# Power_Input.net
KiCad netlist of a schematic drawn in Altium Designer
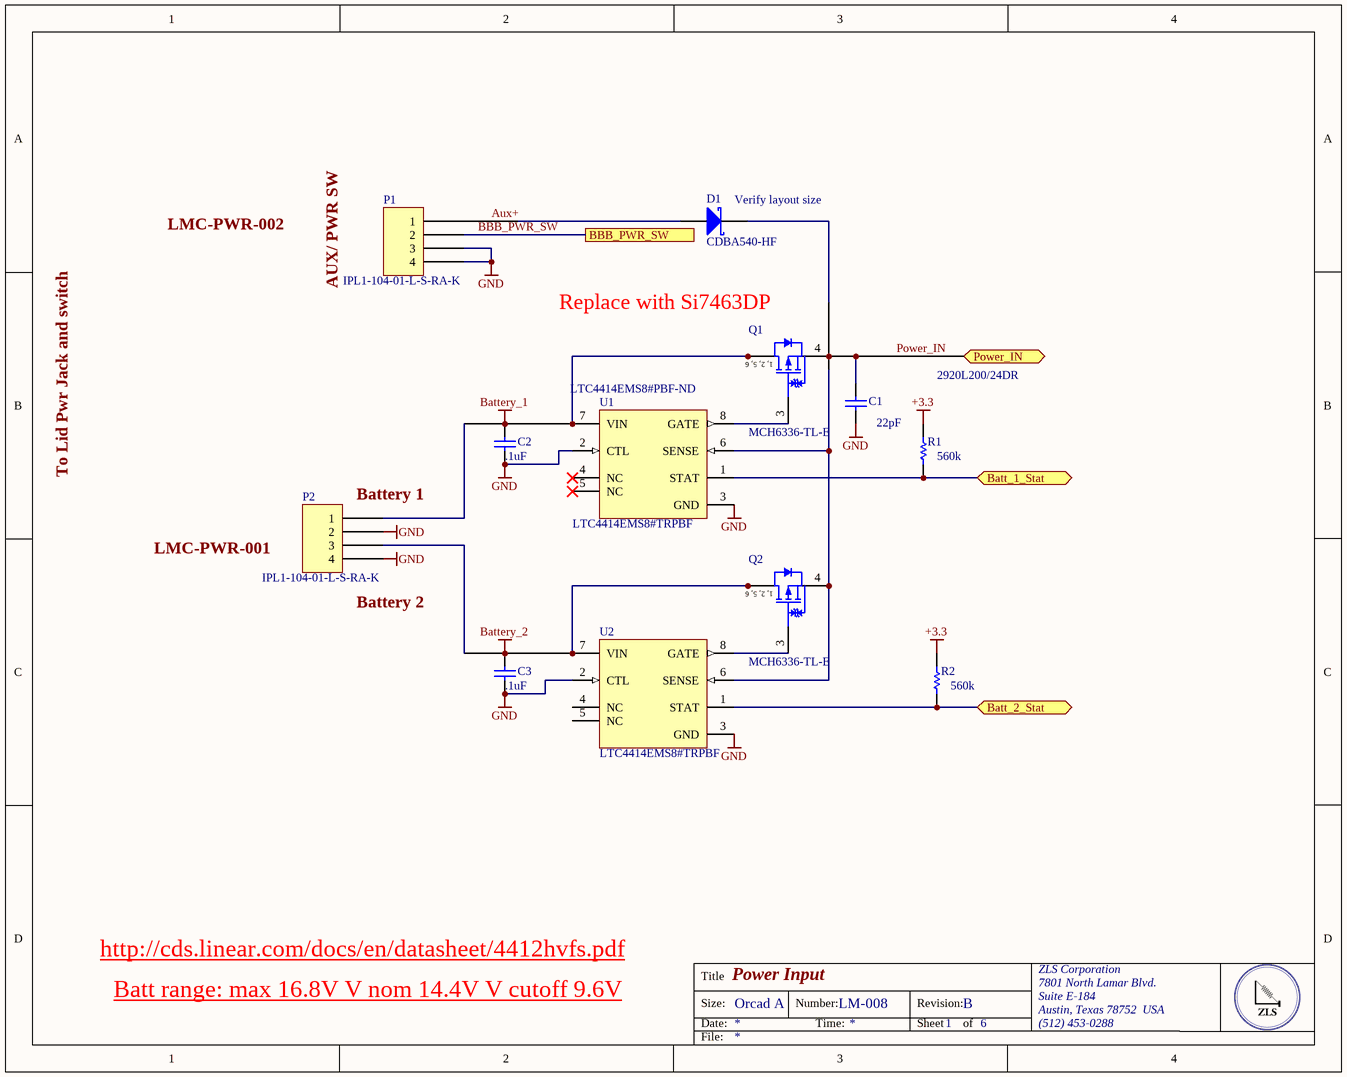
[diagram p0: Power_Input.SchDoc]

(export (version "E")
  (design (tool "Eeschema 10.0.6"))
  (components
    (comp (ref "C1")
      (value "CAP CER 10UF 6.3V X5R 1206")
      (footprint "CAPC1206(3216)130_N")
      (fields
        (field (name "MANUFACTURER") "Taiyo Yuden")
        (field (name "MANUFACTURER PART NUMBER") "JMK316BJ106ML-T")
        (field (name "TOLERANCE") "±20%")
        (field (name "CAPACITANCE") "22pF")
      )
      (libsource (lib "Altium Content Vault") (part "CMP-1037-04913-1"))
    )
    (comp (ref "C2")
      (value "CAP CER 10UF 6.3V X5R 1206")
      (footprint "CAPC1206(3216)130_N")
      (fields
        (field (name "MANUFACTURER") "Taiyo Yuden")
        (field (name "MANUFACTURER PART NUMBER") "JMK316BJ106ML-T")
        (field (name "TOLERANCE") "±20%")
        (field (name "CAPACITANCE") ".1uF")
      )
      (libsource (lib "Altium Content Vault") (part "CMP-1037-04913-1"))
    )
    (comp (ref "C3")
      (value "CAP CER 10UF 6.3V X5R 1206")
      (footprint "CAPC1206(3216)130_N")
      (fields
        (field (name "MANUFACTURER") "Taiyo Yuden")
        (field (name "MANUFACTURER PART NUMBER") "JMK316BJ106ML-T")
        (field (name "TOLERANCE") "±20%")
        (field (name "CAPACITANCE") ".1uF")
      )
      (libsource (lib "Altium Content Vault") (part "CMP-1037-04913-1"))
    )
    (comp (ref "D1")
      (value "CDBA540-HF")
      (footprint "VISH-DO-214AC-2_M")
      (description "DIODE SCHOTTKY 40V 5A DO214AB")
      (fields (field (name "MANUFACTURER") "Comchip Technology"))
      (libsource (lib "Miscellaneous Devices") (part "D Schottky"))
    )
    (comp (ref "P1")
      (value "IPL1-104-01-L-S-RA-K")
      (footprint "IPL1-104-01-L-S-RA-K")
      (fields
        (field (name "MANUFACTURER") "Samtec Inc.")
        (field (name "MANUFACTURER PART NUMBER") "IPL1-104-01-L-S-RA-K")
      )
      (libsource (lib "ZLS_Schematic_lib") (part "IPL1-104-01-L-S-RA-K"))
    )
    (comp (ref "P2")
      (value "IPL1-104-01-L-S-RA-K")
      (footprint "IPL1-104-01-L-S-RA-K")
      (fields
        (field (name "MANUFACTURER") "Samtec Inc.")
        (field (name "MANUFACTURER PART NUMBER") "IPL1-104-01-L-S-RA-K")
      )
      (libsource (lib "ZLS_Schematic_lib") (part "IPL1-104-01-L-S-RA-K"))
    )
    (comp (ref "Q1")
      (value "MCH6336-TL-E")
      (footprint "ONSC-MCPH-6_V")
      (description "P-Channel Power MOSFET, -12 V, -5 A, 43 mOhm, Single, 6-Pin MCPH, Pb-Free, Tape and Reel")
      (fields (field (name "MANUFACTURER") "ON Semiconductor"))
      (libsource (lib "Altium Content Vault") (part "CMP-1058-00598-1"))
    )
    (comp (ref "Q2")
      (value "MCH6336-TL-E")
      (footprint "ONSC-MCPH-6_V")
      (description "P-Channel Power MOSFET, -12 V, -5 A, 43 mOhm, Single, 6-Pin MCPH, Pb-Free, Tape and Reel")
      (fields (field (name "MANUFACTURER") "ON Semiconductor"))
      (libsource (lib "Altium Content Vault") (part "CMP-1058-00598-1"))
    )
    (comp (ref "R1")
      (value "560k")
      (footprint "RESC0402(1005)_L")
      (description "RES SMD 560K OHM 1% 1/10W 0402")
      (fields
        (field (name "MANUFACTURER") "Panasonic Electronic Components")
        (field (name "MANUFACTURER PART NUMBER") "ERJ-2RKF5603X")
      )
      (libsource (lib "Altium Content Vault") (part "CMP-1011-00927-1"))
    )
    (comp (ref "R2")
      (value "560k")
      (footprint "RESC0402(1005)_L")
      (description "RES SMD 560K OHM 1% 1/10W 0402")
      (fields
        (field (name "MANUFACTURER") "Panasonic Electronic Components")
        (field (name "MANUFACTURER PART NUMBER") "ERJ-2RKF5603X")
      )
      (libsource (lib "Altium Content Vault") (part "CMP-1011-00927-1"))
    )
    (comp (ref "U1")
      (value "LTC4414EMS8#TRPBF")
      (footprint "LT-MS8-8_L")
      (fields
        (field (name "SUPPLIER PART NUMBER 1") "LTC4414EMS8#PBF-ND")
        (field (name "MANUFACTURER") "Linear Technology/Analog Devices")
        (field (name "MANUFACTURER PART NUMBER") "LTC4414EMS8#PBF")
        (field (name "BASE PART NUMBER") "LTC4414")
      )
      (libsource (lib "Altium Content Vault") (part "CMP-0479-00214-1"))
    )
    (comp (ref "U2")
      (value "LTC4414EMS8#TRPBF")
      (footprint "LT-MS8-8_L")
      (fields
        (field (name "MANUFACTURER") "Linear Technology/Analog Devices")
        (field (name "MANUFACTURER PART NUMBER") "LTC4414EMS8#PBF")
        (field (name "BASE PART NUMBER") "LTC4414")
      )
      (libsource (lib "Altium Content Vault") (part "CMP-0479-00214-1"))
    )
  )
  (nets
    (net (code "1") (name "+3.3") (class "Default")
      (node (ref "R1") (pin "2") (pinfunction "2_2") (pintype "passive"))
      (node (ref "R2") (pin "2") (pinfunction "2_2") (pintype "passive"))
    )
    (net (code "2") (name "/Aux+") (class "Default")
      (node (ref "D1") (pin "1") (pinfunction "A_1") (pintype "passive"))
      (node (ref "P1") (pin "1") (pinfunction "1_1") (pintype "passive"))
    )
    (net (code "3") (name "/BBB_PWR_SW") (class "Default")
      (node (ref "P1") (pin "2") (pinfunction "2_2") (pintype "passive"))
    )
    (net (code "4") (name "/Batt_1_Stat") (class "Default")
      (node (ref "R1") (pin "1") (pinfunction "1_1") (pintype "passive"))
      (node (ref "U1") (pin "1") (pinfunction "STAT_1") (pintype "open_collector"))
    )
    (net (code "5") (name "/Batt_2_Stat") (class "Default")
      (node (ref "R2") (pin "1") (pinfunction "1_1") (pintype "passive"))
      (node (ref "U2") (pin "1") (pinfunction "STAT_1") (pintype "open_collector"))
    )
    (net (code "6") (name "/Power_IN") (class "Default")
      (node (ref "C1") (pin "2") (pinfunction "2_2") (pintype "passive"))
      (node (ref "D1") (pin "2") (pinfunction "K_2") (pintype "passive"))
      (node (ref "Q1") (pin "4") (pinfunction "S_4") (pintype "passive"))
      (node (ref "Q2") (pin "4") (pinfunction "S_4") (pintype "passive"))
      (node (ref "U1") (pin "6") (pinfunction "SENSE_6") (pintype "input"))
      (node (ref "U2") (pin "6") (pinfunction "SENSE_6") (pintype "input"))
    )
    (net (code "7") (name "Battery_1") (class "Default")
      (node (ref "C2") (pin "2") (pinfunction "2_2") (pintype "passive"))
      (node (ref "P2") (pin "1") (pinfunction "1_1") (pintype "passive"))
      (node (ref "Q1") (pin "1") (pinfunction "D_1") (pintype "passive"))
      (node (ref "Q1") (pin "2") (pinfunction "D_2") (pintype "passive"))
      (node (ref "Q1") (pin "5") (pinfunction "D_5") (pintype "passive"))
      (node (ref "Q1") (pin "6") (pinfunction "D_6") (pintype "passive"))
      (node (ref "U1") (pin "7") (pinfunction "VIN_7") (pintype "power_in"))
    )
    (net (code "8") (name "Battery_2") (class "Default")
      (node (ref "C3") (pin "2") (pinfunction "2_2") (pintype "passive"))
      (node (ref "P2") (pin "3") (pinfunction "3_3") (pintype "passive"))
      (node (ref "Q2") (pin "1") (pinfunction "D_1") (pintype "passive"))
      (node (ref "Q2") (pin "2") (pinfunction "D_2") (pintype "passive"))
      (node (ref "Q2") (pin "5") (pinfunction "D_5") (pintype "passive"))
      (node (ref "Q2") (pin "6") (pinfunction "D_6") (pintype "passive"))
      (node (ref "U2") (pin "7") (pinfunction "VIN_7") (pintype "power_in"))
    )
    (net (code "9") (name "GND") (class "Default")
      (node (ref "C1") (pin "1") (pinfunction "1_1") (pintype "passive"))
      (node (ref "C2") (pin "1") (pinfunction "1_1") (pintype "passive"))
      (node (ref "C3") (pin "1") (pinfunction "1_1") (pintype "passive"))
      (node (ref "P1") (pin "3") (pinfunction "3_3") (pintype "passive"))
      (node (ref "P1") (pin "4") (pinfunction "4_4") (pintype "passive"))
      (node (ref "P2") (pin "2") (pinfunction "2_2") (pintype "passive"))
      (node (ref "P2") (pin "4") (pinfunction "4_4") (pintype "passive"))
      (node (ref "U1") (pin "2") (pinfunction "CTL_2") (pintype "input"))
      (node (ref "U1") (pin "3") (pinfunction "GND_3") (pintype "power_in"))
      (node (ref "U2") (pin "2") (pinfunction "CTL_2") (pintype "input"))
      (node (ref "U2") (pin "3") (pinfunction "GND_3") (pintype "power_in"))
    )
    (net (code "10") (name "Net-(Q1-G)") (class "Default")
      (node (ref "Q1") (pin "3") (pinfunction "G_3") (pintype "passive"))
      (node (ref "U1") (pin "8") (pinfunction "GATE_8") (pintype "output"))
    )
    (net (code "11") (name "Net-(Q2-G)") (class "Default")
      (node (ref "Q2") (pin "3") (pinfunction "G_3") (pintype "passive"))
      (node (ref "U2") (pin "8") (pinfunction "GATE_8") (pintype "output"))
    )
    (net (code "12") (name "unconnected-(U1-NC-Pad4)") (class "Default")
      (node (ref "U1") (pin "4") (pinfunction "NC_4") (pintype "passive+no_connect"))
    )
    (net (code "13") (name "unconnected-(U1-NC-Pad5)") (class "Default")
      (node (ref "U1") (pin "5") (pinfunction "NC_5") (pintype "passive+no_connect"))
    )
    (net (code "14") (name "unconnected-(U2-NC-Pad4)") (class "Default")
      (node (ref "U2") (pin "4") (pinfunction "NC_4") (pintype "passive"))
    )
    (net (code "15") (name "unconnected-(U2-NC-Pad5)") (class "Default")
      (node (ref "U2") (pin "5") (pinfunction "NC_5") (pintype "passive"))
    )
  )
)
